# Arduino_Engine_Room.net
KiCad netlist of a schematic drawn in EAGLE
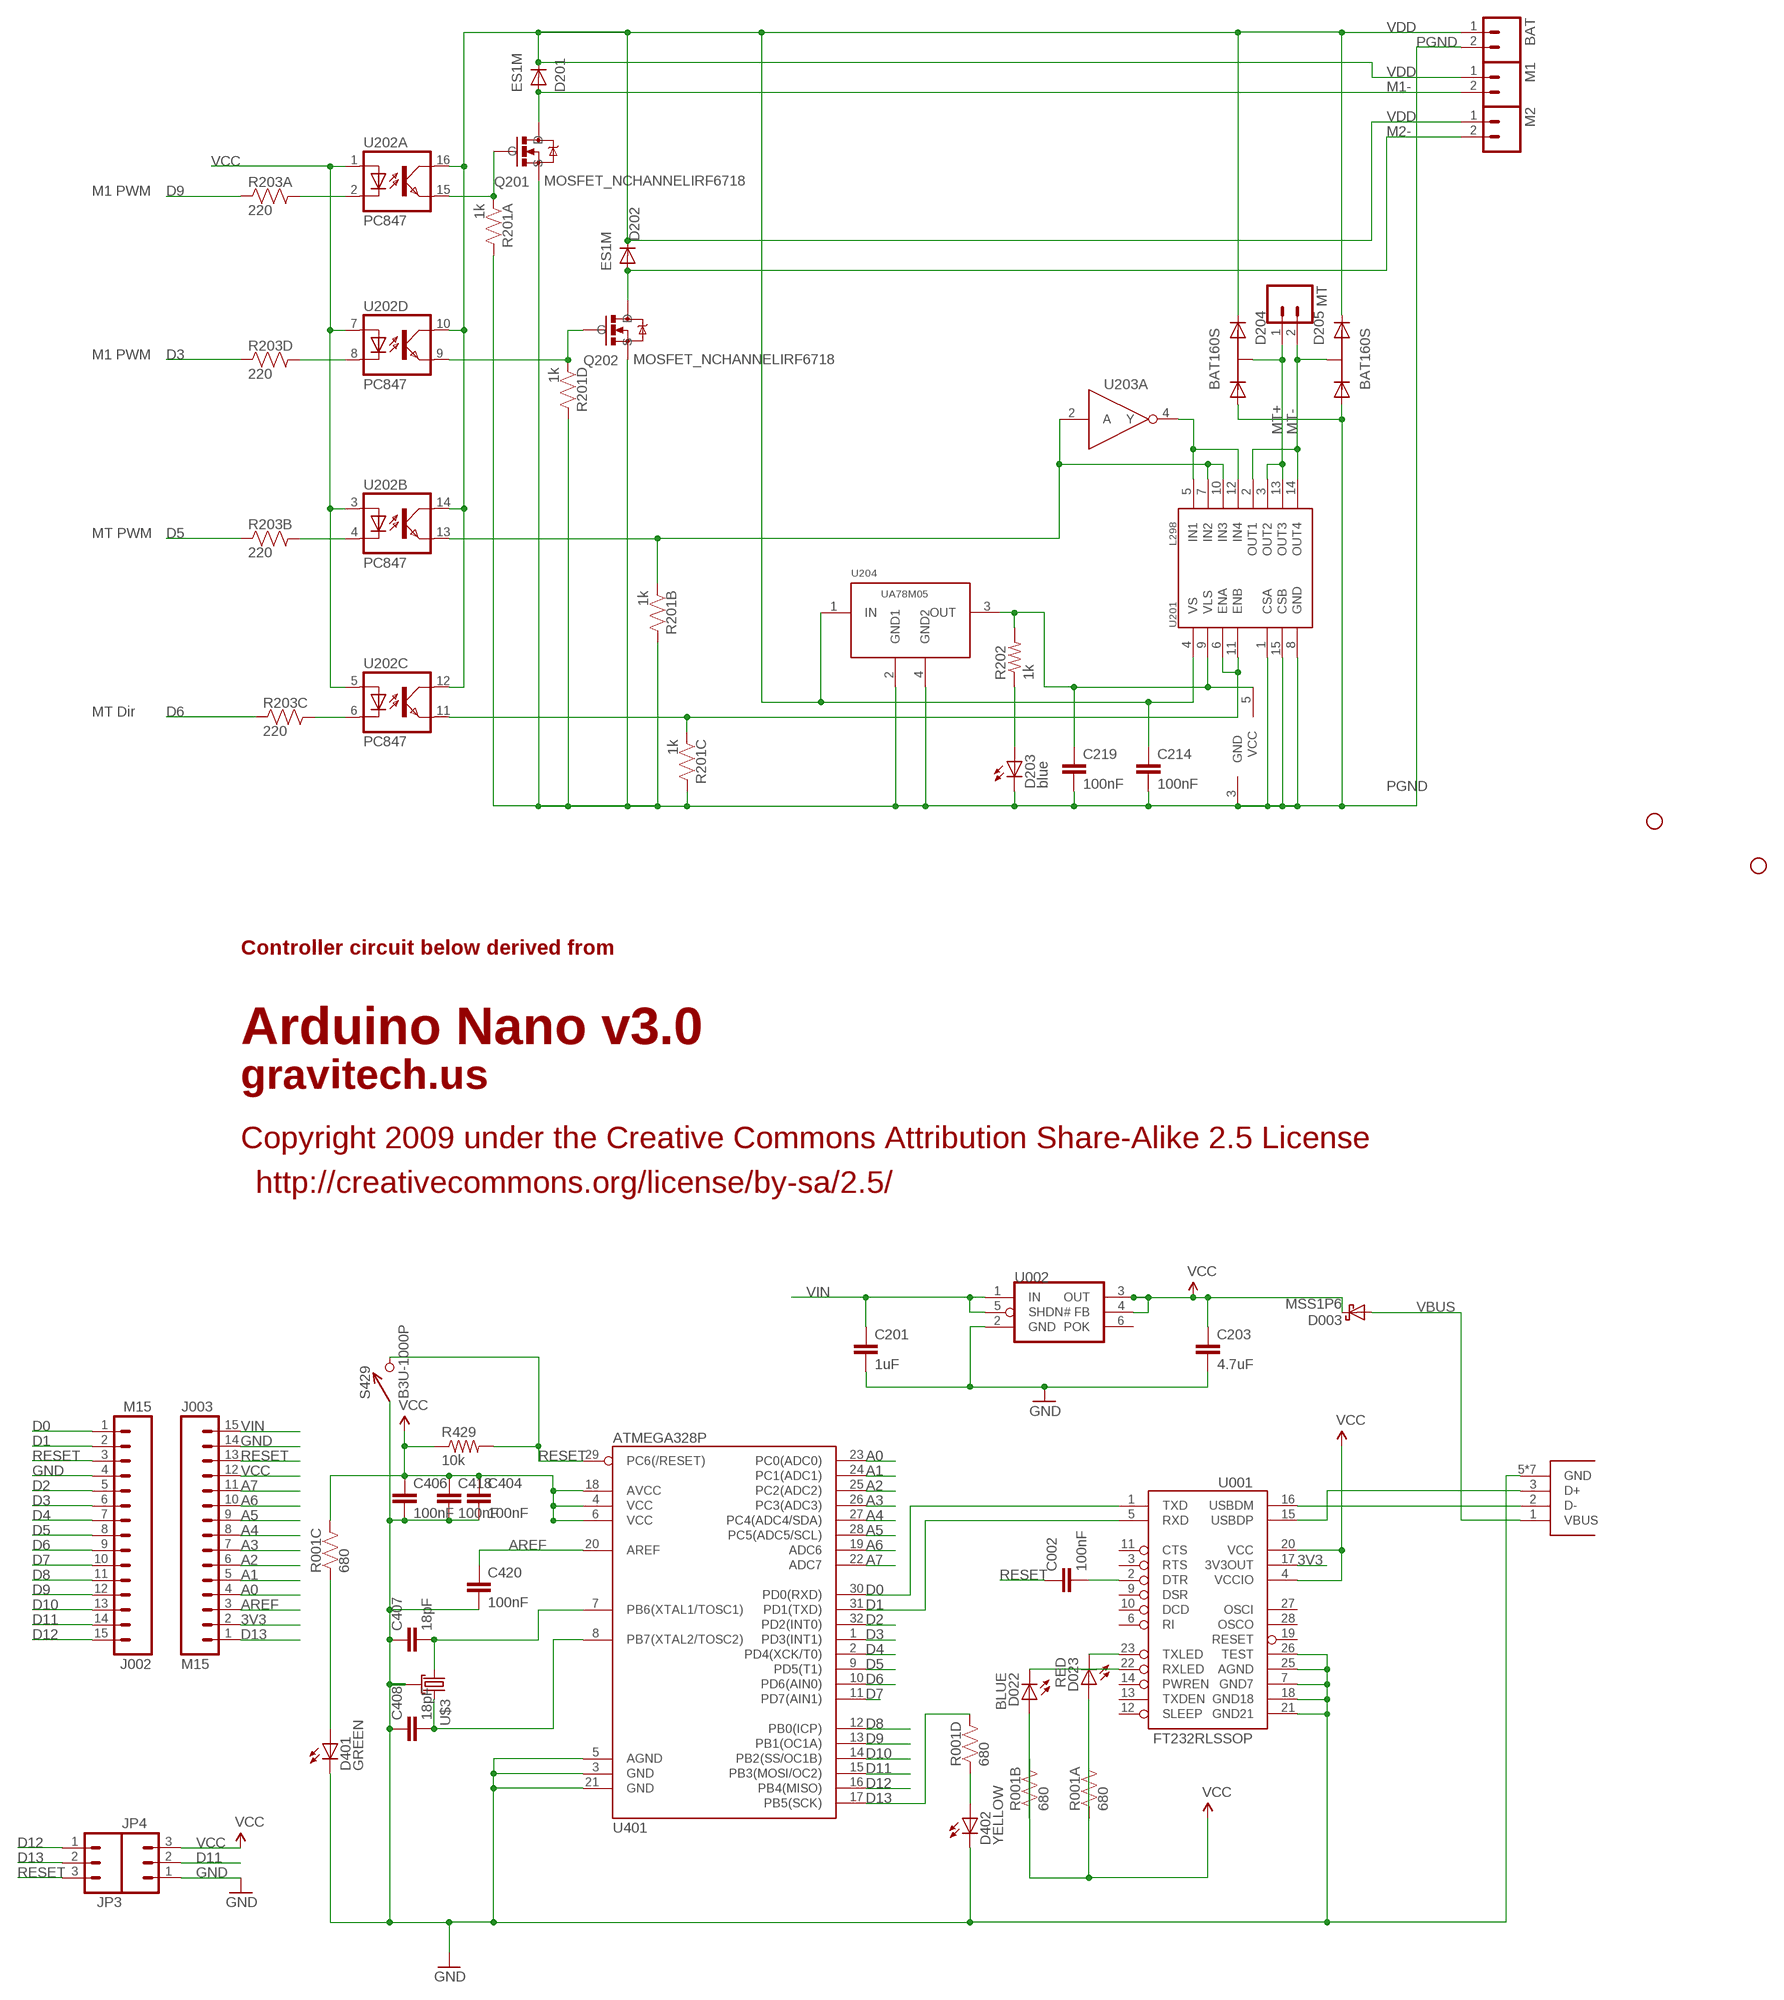
[diagram p0: schematic, sheet 1]

(export (version "E")
  (design (tool "Eeschema 10.0.6"))
  (components
    (comp (ref "BAT")
      (value "M02PTH4")
      (footprint "eagle-import:1X02_XTRA_BIG")
      (libsource (lib "eagle-import") (part "M02PTH4"))
    )
    (comp (ref "C002")
      (value "100nF")
      (footprint "eagle-import:0402-CAP")
      (libsource (lib "eagle-import") (part "CAP0402-CAP"))
    )
    (comp (ref "C201")
      (value "1uF")
      (footprint "eagle-import:0402-CAP")
      (libsource (lib "eagle-import") (part "CAP0402-CAP"))
    )
    (comp (ref "C203")
      (value "4.7uF")
      (footprint "eagle-import:0402-CAP")
      (libsource (lib "eagle-import") (part "CAP0402-CAP"))
    )
    (comp (ref "C214")
      (value "100nF")
      (footprint "eagle-import:0402-CAP")
      (libsource (lib "eagle-import") (part "CAP0402-CAP"))
    )
    (comp (ref "C219")
      (value "100nF")
      (footprint "eagle-import:0402-CAP")
      (libsource (lib "eagle-import") (part "CAP0402-CAP"))
    )
    (comp (ref "C404")
      (value "100nF")
      (footprint "eagle-import:0402-CAP")
      (libsource (lib "eagle-import") (part "CAP0402-CAP"))
    )
    (comp (ref "C406")
      (value "100nF")
      (footprint "eagle-import:0402-CAP")
      (libsource (lib "eagle-import") (part "CAP0402-CAP"))
    )
    (comp (ref "C407")
      (value "18pF")
      (footprint "eagle-import:0402-CAP")
      (libsource (lib "eagle-import") (part "CAP0402-CAP"))
    )
    (comp (ref "C408")
      (value "18pF")
      (footprint "eagle-import:0402-CAP")
      (libsource (lib "eagle-import") (part "CAP0402-CAP"))
    )
    (comp (ref "C418")
      (value "100nF")
      (footprint "eagle-import:0402-CAP")
      (libsource (lib "eagle-import") (part "CAP0402-CAP"))
    )
    (comp (ref "C420")
      (value "100nF")
      (footprint "eagle-import:0402-CAP")
      (libsource (lib "eagle-import") (part "CAP0402-CAP"))
    )
    (comp (ref "D003")
      (value "MSS1P6")
      (footprint "eagle-import:MICROSMP")
      (libsource (lib "eagle-import") (part "MSS1P6"))
    )
    (comp (ref "D022")
      (value "BLUE")
      (footprint "eagle-import:LED-0603")
      (libsource (lib "eagle-import") (part "SparkFun-LED_LED0603"))
    )
    (comp (ref "D023")
      (value "RED")
      (footprint "eagle-import:LED-0603")
      (libsource (lib "eagle-import") (part "SparkFun-LED_LED0603"))
    )
    (comp (ref "D201")
      (value "ES1M")
      (footprint "eagle-import:DO-214AC")
      (libsource (lib "eagle-import") (part "DIODE-DO-214AC"))
    )
    (comp (ref "D202")
      (value "ES1M")
      (footprint "eagle-import:DO-214AC")
      (libsource (lib "eagle-import") (part "DIODE-DO-214AC"))
    )
    (comp (ref "D203")
      (value "blue")
      (footprint "eagle-import:LED-0603")
      (libsource (lib "eagle-import") (part "LED0603"))
    )
    (comp (ref "D204")
      (value "BAT160S")
      (footprint "eagle-import:SOT-223")
      (libsource (lib "eagle-import") (part "BAT160S"))
    )
    (comp (ref "D205")
      (value "BAT160S")
      (footprint "eagle-import:SOT-223")
      (libsource (lib "eagle-import") (part "BAT160S"))
    )
    (comp (ref "D401")
      (value "GREEN")
      (footprint "eagle-import:LED-0603")
      (libsource (lib "eagle-import") (part "SparkFun-LED_LED0603"))
    )
    (comp (ref "D402")
      (value "YELLOW")
      (footprint "eagle-import:LED-0603")
      (libsource (lib "eagle-import") (part "SparkFun-LED_LED0603"))
    )
    (comp (ref "J001")
      (value "USB_MICROB_JSTGCT")
      (footprint "eagle-import:USB_MICROB_3075")
      (libsource (lib "eagle-import") (part "USB_MICROB_JSTGCT"))
    )
    (comp (ref "J002")
      (value "M15")
      (footprint "eagle-import:1X15")
      (libsource (lib "eagle-import") (part "M15"))
    )
    (comp (ref "J003")
      (value "M15")
      (footprint "eagle-import:1X15")
      (libsource (lib "eagle-import") (part "M15"))
    )
    (comp (ref "JP1")
      (value "STAND-OFF")
      (footprint "eagle-import:STAND-OFF")
      (libsource (lib "eagle-import") (part "STAND-OFF"))
    )
    (comp (ref "JP2")
      (value "STAND-OFF")
      (footprint "eagle-import:STAND-OFF")
      (libsource (lib "eagle-import") (part "STAND-OFF"))
    )
    (comp (ref "JP3")
      (value "M03PTH")
      (footprint "eagle-import:1X03")
      (libsource (lib "eagle-import") (part "M03PTH"))
    )
    (comp (ref "JP4")
      (value "M03PTH")
      (footprint "eagle-import:1X03")
      (libsource (lib "eagle-import") (part "M03PTH"))
    )
    (comp (ref "M1")
      (value "M02PTH4")
      (footprint "eagle-import:1X02_XTRA_BIG")
      (libsource (lib "eagle-import") (part "M02PTH4"))
    )
    (comp (ref "M2")
      (value "M02PTH4")
      (footprint "eagle-import:1X02_XTRA_BIG")
      (libsource (lib "eagle-import") (part "M02PTH4"))
    )
    (comp (ref "MT")
      (value "M02PTH")
      (footprint "eagle-import:1X02")
      (libsource (lib "eagle-import") (part "M02PTH"))
    )
    (comp (ref "Q201")
      (value "MOSFET_NCHANNELIRF6718")
      (footprint "eagle-import:DIRECTFET_L6")
      (libsource (lib "eagle-import") (part "MOSFET_NCHANNELIRF6718"))
    )
    (comp (ref "Q202")
      (value "MOSFET_NCHANNELIRF6718")
      (footprint "eagle-import:DIRECTFET_L6")
      (libsource (lib "eagle-import") (part "MOSFET_NCHANNELIRF6718"))
    )
    (comp (ref "R001")
      (value "680")
      (footprint "eagle-import:CRA04")
      (fields (field (name "DIGIKEY") "CRA4S8680CT-ND"))
      (libsource (lib "eagle-import") (part "RP404"))
    )
    (comp (ref "R201")
      (value "1k")
      (footprint "eagle-import:CRA04")
      (libsource (lib "eagle-import") (part "RP404"))
    )
    (comp (ref "R202")
      (value "1k")
      (footprint "eagle-import:0402-RES")
      (libsource (lib "eagle-import") (part "RESISTOR0402-RES"))
    )
    (comp (ref "R203")
      (value "220")
      (footprint "eagle-import:CRA04")
      (libsource (lib "eagle-import") (part "RP404"))
    )
    (comp (ref "R429")
      (value "10k")
      (footprint "eagle-import:0402-RES")
      (libsource (lib "eagle-import") (part "SparkFun-Passives_RESISTOR0402-RES"))
    )
    (comp (ref "S429")
      (value "B3U-1000P")
      (footprint "eagle-import:B3U-1000P")
      (libsource (lib "eagle-import") (part "B3U-1000P"))
    )
    (comp (ref "U$3")
      (value "CX2520")
      (footprint "eagle-import:CRYSTAL_SMD_2MM_2_5MM")
      (libsource (lib "eagle-import") (part "CX2520"))
    )
    (comp (ref "U001")
      (value "FT232RLSSOP")
      (footprint "eagle-import:SSOP28DB")
      (libsource (lib "eagle-import") (part "FT232RLSSOP"))
    )
    (comp (ref "U002")
      (value "MAX8881")
      (footprint "eagle-import:SOT-23-6")
      (libsource (lib "eagle-import") (part "MAX8881"))
    )
    (comp (ref "U201")
      (value "L298")
      (footprint "eagle-import:MULTIWATT15")
      (libsource (lib "eagle-import") (part "L298"))
    )
    (comp (ref "U202")
      (value "PC847")
      (footprint "eagle-import:DIL16")
      (libsource (lib "eagle-import") (part "PC847"))
    )
    (comp (ref "U203")
      (value "MC74VHC1G04")
      (footprint "eagle-import:SOT-23-5")
      (libsource (lib "eagle-import") (part "MC74VHC1G04"))
    )
    (comp (ref "U204")
      (value "UA78M05")
      (footprint "eagle-import:SOT223")
      (libsource (lib "eagle-import") (part "UA78M05"))
    )
    (comp (ref "U401")
      (value "ATMEGA328P")
      (footprint "eagle-import:TQFP32-08")
      (libsource (lib "eagle-import") (part "ATMEGA168"))
    )
  )
  (nets
    (net (code "1") (name "/3V3") (class "Default")
      (node (ref "J003") (pin "2") (pinfunction "2_2") (pintype "passive"))
      (node (ref "U001") (pin "17") (pinfunction "3V3OUT_17") (pintype "output"))
    )
    (net (code "2") (name "/A0") (class "Default")
      (node (ref "J003") (pin "4") (pinfunction "4_4") (pintype "passive"))
      (node (ref "U401") (pin "23") (pinfunction "PC0(ADC0)_23") (pintype "bidirectional"))
    )
    (net (code "3") (name "/A1") (class "Default")
      (node (ref "J003") (pin "5") (pinfunction "5_5") (pintype "passive"))
      (node (ref "U401") (pin "24") (pinfunction "PC1(ADC1)_24") (pintype "bidirectional"))
    )
    (net (code "4") (name "/A2") (class "Default")
      (node (ref "J003") (pin "6") (pinfunction "6_6") (pintype "passive"))
      (node (ref "U401") (pin "25") (pinfunction "PC2(ADC2)_25") (pintype "bidirectional"))
    )
    (net (code "5") (name "/A3") (class "Default")
      (node (ref "J003") (pin "7") (pinfunction "7_7") (pintype "passive"))
      (node (ref "U401") (pin "26") (pinfunction "PC3(ADC3)_26") (pintype "bidirectional"))
    )
    (net (code "6") (name "/A4") (class "Default")
      (node (ref "J003") (pin "8") (pinfunction "8_8") (pintype "passive"))
      (node (ref "U401") (pin "27") (pinfunction "PC4(ADC4/SDA)_27") (pintype "bidirectional"))
    )
    (net (code "7") (name "/A5") (class "Default")
      (node (ref "J003") (pin "9") (pinfunction "9_9") (pintype "passive"))
      (node (ref "U401") (pin "28") (pinfunction "PC5(ADC5/SCL)_28") (pintype "bidirectional"))
    )
    (net (code "8") (name "/A6") (class "Default")
      (node (ref "J003") (pin "10") (pinfunction "10_10") (pintype "passive"))
      (node (ref "U401") (pin "19") (pinfunction "ADC6_19") (pintype "bidirectional"))
    )
    (net (code "9") (name "/A7") (class "Default")
      (node (ref "J003") (pin "11") (pinfunction "11_11") (pintype "passive"))
      (node (ref "U401") (pin "22") (pinfunction "ADC7_22") (pintype "bidirectional"))
    )
    (net (code "10") (name "/AREF") (class "Default")
      (node (ref "C420") (pin "1") (pinfunction "1_1") (pintype "passive"))
      (node (ref "J003") (pin "3") (pinfunction "3_3") (pintype "passive"))
      (node (ref "U401") (pin "20") (pinfunction "AREF_20") (pintype "bidirectional"))
    )
    (net (code "11") (name "/D0") (class "Default")
      (node (ref "J002") (pin "1") (pinfunction "1_1") (pintype "passive"))
      (node (ref "U001") (pin "1") (pinfunction "TXD_1") (pintype "output"))
      (node (ref "U401") (pin "30") (pinfunction "PD0(RXD)_30") (pintype "bidirectional"))
    )
    (net (code "12") (name "/D1") (class "Default")
      (node (ref "J002") (pin "2") (pinfunction "2_2") (pintype "passive"))
      (node (ref "U001") (pin "5") (pinfunction "RXD_5") (pintype "input"))
      (node (ref "U401") (pin "31") (pinfunction "PD1(TXD)_31") (pintype "bidirectional"))
    )
    (net (code "13") (name "/D2") (class "Default")
      (node (ref "J002") (pin "5") (pinfunction "5_5") (pintype "passive"))
      (node (ref "U401") (pin "32") (pinfunction "PD2(INT0)_32") (pintype "bidirectional"))
    )
    (net (code "14") (name "/D3") (class "Default")
      (node (ref "J002") (pin "6") (pinfunction "6_6") (pintype "passive"))
      (node (ref "R203") (pin "4") (pinfunction "1_4") (pintype "passive"))
      (node (ref "U401") (pin "1") (pinfunction "PD3(INT1)_1") (pintype "bidirectional"))
    )
    (net (code "15") (name "/D4") (class "Default")
      (node (ref "J002") (pin "7") (pinfunction "7_7") (pintype "passive"))
      (node (ref "U401") (pin "2") (pinfunction "PD4(XCK/T0)_2") (pintype "bidirectional"))
    )
    (net (code "16") (name "/D5") (class "Default")
      (node (ref "J002") (pin "8") (pinfunction "8_8") (pintype "passive"))
      (node (ref "R203") (pin "2") (pinfunction "1_2") (pintype "passive"))
      (node (ref "U401") (pin "9") (pinfunction "PD5(T1)_9") (pintype "bidirectional"))
    )
    (net (code "17") (name "/D6") (class "Default")
      (node (ref "J002") (pin "9") (pinfunction "9_9") (pintype "passive"))
      (node (ref "R203") (pin "3") (pinfunction "1_3") (pintype "passive"))
      (node (ref "U401") (pin "10") (pinfunction "PD6(AIN0)_10") (pintype "bidirectional"))
    )
    (net (code "18") (name "/D7") (class "Default")
      (node (ref "J002") (pin "10") (pinfunction "10_10") (pintype "passive"))
      (node (ref "U401") (pin "11") (pinfunction "PD7(AIN1)_11") (pintype "bidirectional"))
    )
    (net (code "19") (name "/D8") (class "Default")
      (node (ref "J002") (pin "11") (pinfunction "11_11") (pintype "passive"))
      (node (ref "U401") (pin "12") (pinfunction "PB0(ICP)_12") (pintype "bidirectional"))
    )
    (net (code "20") (name "/D9") (class "Default")
      (node (ref "J002") (pin "12") (pinfunction "12_12") (pintype "passive"))
      (node (ref "R203") (pin "1") (pinfunction "1_1") (pintype "passive"))
      (node (ref "U401") (pin "13") (pinfunction "PB1(OC1A)_13") (pintype "bidirectional"))
    )
    (net (code "21") (name "/D10") (class "Default")
      (node (ref "J002") (pin "13") (pinfunction "13_13") (pintype "passive"))
      (node (ref "U401") (pin "14") (pinfunction "PB2(SS/OC1B)_14") (pintype "bidirectional"))
    )
    (net (code "22") (name "/D11") (class "Default")
      (node (ref "J002") (pin "14") (pinfunction "14_14") (pintype "passive"))
      (node (ref "JP4") (pin "2") (pinfunction "2_2") (pintype "passive"))
      (node (ref "U401") (pin "15") (pinfunction "PB3(MOSI/OC2)_15") (pintype "bidirectional"))
    )
    (net (code "23") (name "/D12") (class "Default")
      (node (ref "J002") (pin "15") (pinfunction "15_15") (pintype "passive"))
      (node (ref "JP3") (pin "1") (pinfunction "1_1") (pintype "passive"))
      (node (ref "U401") (pin "16") (pinfunction "PB4(MISO)_16") (pintype "bidirectional"))
    )
    (net (code "24") (name "/D13") (class "Default")
      (node (ref "J003") (pin "1") (pinfunction "1_1") (pintype "passive"))
      (node (ref "JP3") (pin "2") (pinfunction "2_2") (pintype "passive"))
      (node (ref "R001") (pin "5") (pinfunction "2_5") (pintype "passive"))
      (node (ref "U401") (pin "17") (pinfunction "PB5(SCK)_17") (pintype "bidirectional"))
    )
    (net (code "25") (name "/M1-") (class "Default")
      (node (ref "D201") (pin "A") (pinfunction "A_A") (pintype "passive"))
      (node (ref "M1") (pin "2") (pinfunction "2_2") (pintype "passive"))
      (node (ref "Q201") (pin "D1") (pinfunction "D_D1") (pintype "passive"))
      (node (ref "Q201") (pin "D2") (pinfunction "D_D2") (pintype "passive"))
    )
    (net (code "26") (name "/M2-") (class "Default")
      (node (ref "D202") (pin "A") (pinfunction "A_A") (pintype "passive"))
      (node (ref "M2") (pin "2") (pinfunction "2_2") (pintype "passive"))
      (node (ref "Q202") (pin "D1") (pinfunction "D_D1") (pintype "passive"))
      (node (ref "Q202") (pin "D2") (pinfunction "D_D2") (pintype "passive"))
    )
    (net (code "27") (name "/MT+") (class "Default")
      (node (ref "D204") (pin "4") (pinfunction "K1A2_4") (pintype "passive"))
      (node (ref "MT") (pin "1") (pinfunction "1_1") (pintype "passive"))
      (node (ref "U201") (pin "13") (pinfunction "OUT3_13") (pintype "bidirectional"))
      (node (ref "U201") (pin "3") (pinfunction "OUT2_3") (pintype "bidirectional"))
    )
    (net (code "28") (name "/MT-") (class "Default")
      (node (ref "D205") (pin "4") (pinfunction "K1A2_4") (pintype "passive"))
      (node (ref "MT") (pin "2") (pinfunction "2_2") (pintype "passive"))
      (node (ref "U201") (pin "14") (pinfunction "OUT4_14") (pintype "bidirectional"))
      (node (ref "U201") (pin "2") (pinfunction "OUT1_2") (pintype "bidirectional"))
    )
    (net (code "29") (name "/PGND") (class "Default")
      (node (ref "BAT") (pin "2") (pinfunction "2_2") (pintype "passive"))
      (node (ref "C214") (pin "2") (pinfunction "2_2") (pintype "passive"))
      (node (ref "C219") (pin "2") (pinfunction "2_2") (pintype "passive"))
      (node (ref "D203") (pin "C") (pinfunction "C_C") (pintype "passive"))
      (node (ref "D204") (pin "1") (pinfunction "A1_1") (pintype "passive"))
      (node (ref "D205") (pin "1") (pinfunction "A1_1") (pintype "passive"))
      (node (ref "Q201") (pin "S") (pinfunction "S_S") (pintype "passive"))
      (node (ref "Q202") (pin "S") (pinfunction "S_S") (pintype "passive"))
      (node (ref "R201") (pin "5") (pinfunction "2_5") (pintype "passive"))
      (node (ref "R201") (pin "6") (pinfunction "2_6") (pintype "passive"))
      (node (ref "R201") (pin "7") (pinfunction "2_7") (pintype "passive"))
      (node (ref "R201") (pin "8") (pinfunction "2_8") (pintype "passive"))
      (node (ref "U201") (pin "1") (pinfunction "CSA_1") (pintype "bidirectional"))
      (node (ref "U201") (pin "15") (pinfunction "CSB_15") (pintype "bidirectional"))
      (node (ref "U201") (pin "8") (pinfunction "GND_8") (pintype "bidirectional"))
      (node (ref "U203") (pin "3") (pinfunction "GND_3") (pintype "bidirectional"))
      (node (ref "U204") (pin "2") (pinfunction "GND1_2") (pintype "power_in"))
      (node (ref "U204") (pin "4") (pinfunction "GND2_4") (pintype "power_in"))
    )
    (net (code "30") (name "/RESET") (class "Default")
      (node (ref "C002") (pin "1") (pinfunction "1_1") (pintype "passive"))
      (node (ref "J002") (pin "3") (pinfunction "3_3") (pintype "passive"))
      (node (ref "J003") (pin "13") (pinfunction "13_13") (pintype "passive"))
      (node (ref "JP3") (pin "3") (pinfunction "3_3") (pintype "passive"))
      (node (ref "R429") (pin "2") (pinfunction "2_2") (pintype "passive"))
      (node (ref "S429") (pin "P$2") (pinfunction "2_P$2") (pintype "bidirectional"))
      (node (ref "U401") (pin "29") (pinfunction "PC6(/RESET)_29") (pintype "bidirectional"))
    )
    (net (code "31") (name "/VBUS") (class "Default")
      (node (ref "D003") (pin "A") (pinfunction "A_A") (pintype "passive"))
      (node (ref "J001") (pin "1") (pinfunction "VBUS_1") (pintype "bidirectional"))
    )
    (net (code "32") (name "/VDD") (class "Default")
      (node (ref "BAT") (pin "1") (pinfunction "1_1") (pintype "passive"))
      (node (ref "C214") (pin "1") (pinfunction "1_1") (pintype "passive"))
      (node (ref "D201") (pin "C") (pinfunction "C_C") (pintype "passive"))
      (node (ref "D202") (pin "C") (pinfunction "C_C") (pintype "passive"))
      (node (ref "D204") (pin "3") (pinfunction "K2_3") (pintype "passive"))
      (node (ref "D205") (pin "3") (pinfunction "K2_3") (pintype "passive"))
      (node (ref "M1") (pin "1") (pinfunction "1_1") (pintype "passive"))
      (node (ref "M2") (pin "1") (pinfunction "1_1") (pintype "passive"))
      (node (ref "U201") (pin "4") (pinfunction "VS_4") (pintype "bidirectional"))
      (node (ref "U202") (pin "10") (pinfunction "COL_10") (pintype "passive"))
      (node (ref "U202") (pin "12") (pinfunction "COL_12") (pintype "passive"))
      (node (ref "U202") (pin "14") (pinfunction "COL_14") (pintype "passive"))
      (node (ref "U202") (pin "16") (pinfunction "COL_16") (pintype "passive"))
      (node (ref "U204") (pin "1") (pinfunction "IN_1") (pintype "power_in"))
    )
    (net (code "33") (name "/VIN") (class "Default")
      (node (ref "C201") (pin "1") (pinfunction "1_1") (pintype "passive"))
      (node (ref "J003") (pin "15") (pinfunction "15_15") (pintype "passive"))
      (node (ref "U002") (pin "1") (pinfunction "IN_1") (pintype "bidirectional"))
      (node (ref "U002") (pin "5") (pinfunction "SHDN#_5") (pintype "bidirectional"))
    )
    (net (code "34") (name "GND") (class "Default")
      (node (ref "C201") (pin "2") (pinfunction "2_2") (pintype "passive"))
      (node (ref "C203") (pin "2") (pinfunction "2_2") (pintype "passive"))
      (node (ref "C404") (pin "2") (pinfunction "2_2") (pintype "passive"))
      (node (ref "C406") (pin "2") (pinfunction "2_2") (pintype "passive"))
      (node (ref "C407") (pin "1") (pinfunction "1_1") (pintype "passive"))
      (node (ref "C408") (pin "1") (pinfunction "1_1") (pintype "passive"))
      (node (ref "C418") (pin "2") (pinfunction "2_2") (pintype "passive"))
      (node (ref "C420") (pin "2") (pinfunction "2_2") (pintype "passive"))
      (node (ref "D401") (pin "C") (pinfunction "C_C") (pintype "passive"))
      (node (ref "D402") (pin "C") (pinfunction "C_C") (pintype "passive"))
      (node (ref "J001") (pin "5") (pinfunction "GND_5") (pintype "bidirectional"))
      (node (ref "J001") (pin "P$1") (pinfunction "GND_P$1") (pintype "bidirectional"))
      (node (ref "J001") (pin "P$10") (pinfunction "GND_P$10") (pintype "bidirectional"))
      (node (ref "J001") (pin "P$2") (pinfunction "GND_P$2") (pintype "bidirectional"))
      (node (ref "J001") (pin "P$3") (pinfunction "GND_P$3") (pintype "bidirectional"))
      (node (ref "J001") (pin "P$4") (pinfunction "GND_P$4") (pintype "bidirectional"))
      (node (ref "J001") (pin "P$8") (pinfunction "GND_P$8") (pintype "bidirectional"))
      (node (ref "J002") (pin "4") (pinfunction "4_4") (pintype "passive"))
      (node (ref "J003") (pin "14") (pinfunction "14_14") (pintype "passive"))
      (node (ref "JP4") (pin "1") (pinfunction "1_1") (pintype "passive"))
      (node (ref "S429") (pin "P$1") (pinfunction "1_P$1") (pintype "bidirectional"))
      (node (ref "U$3") (pin "2") (pinfunction "GND_2") (pintype "passive"))
      (node (ref "U$3") (pin "4") (pinfunction "GND_4") (pintype "passive"))
      (node (ref "U001") (pin "18") (pinfunction "GND18_18") (pintype "power_in"))
      (node (ref "U001") (pin "21") (pinfunction "GND21_21") (pintype "power_in"))
      (node (ref "U001") (pin "25") (pinfunction "AGND_25") (pintype "power_in"))
      (node (ref "U001") (pin "26") (pinfunction "TEST_26") (pintype "input"))
      (node (ref "U001") (pin "7") (pinfunction "GND7_7") (pintype "power_in"))
      (node (ref "U002") (pin "2") (pinfunction "GND_2") (pintype "bidirectional"))
      (node (ref "U401") (pin "21") (pinfunction "GND_21") (pintype "bidirectional"))
      (node (ref "U401") (pin "3") (pinfunction "GND_3") (pintype "bidirectional"))
      (node (ref "U401") (pin "5") (pinfunction "AGND_5") (pintype "bidirectional"))
    )
    (net (code "35") (name "Net-(D023-PadA)") (class "Default")
      (node (ref "D023") (pin "A") (pinfunction "A_A") (pintype "passive"))
      (node (ref "R001") (pin "1") (pinfunction "1_1") (pintype "passive"))
    )
    (net (code "36") (name "Net-(D203-PadA)") (class "Default")
      (node (ref "D203") (pin "A") (pinfunction "A_A") (pintype "passive"))
      (node (ref "R202") (pin "1") (pinfunction "1_1") (pintype "passive"))
    )
    (net (code "37") (name "Net-(J001-D+)") (class "Default")
      (node (ref "J001") (pin "3") (pinfunction "D+_3") (pintype "bidirectional"))
      (node (ref "U001") (pin "15") (pinfunction "USBDP_15") (pintype "bidirectional"))
    )
    (net (code "38") (name "Net-(J001-D-)") (class "Default")
      (node (ref "J001") (pin "2") (pinfunction "D-_2") (pintype "bidirectional"))
      (node (ref "U001") (pin "16") (pinfunction "USBDM_16") (pintype "bidirectional"))
    )
    (net (code "39") (name "Net-(R001B-1)") (class "Default")
      (node (ref "D022") (pin "A") (pinfunction "A_A") (pintype "passive"))
      (node (ref "R001") (pin "2") (pinfunction "1_2") (pintype "passive"))
    )
    (net (code "40") (name "Net-(R001C-1)") (class "Default")
      (node (ref "D401") (pin "A") (pinfunction "A_A") (pintype "passive"))
      (node (ref "R001") (pin "3") (pinfunction "1_3") (pintype "passive"))
    )
    (net (code "41") (name "Net-(R001D-1)") (class "Default")
      (node (ref "D402") (pin "A") (pinfunction "A_A") (pintype "passive"))
      (node (ref "R001") (pin "4") (pinfunction "1_4") (pintype "passive"))
    )
    (net (code "42") (name "Net-(R201B-1)") (class "Default")
      (node (ref "R201") (pin "2") (pinfunction "1_2") (pintype "passive"))
      (node (ref "U201") (pin "10") (pinfunction "IN3_10") (pintype "bidirectional"))
      (node (ref "U201") (pin "7") (pinfunction "IN2_7") (pintype "bidirectional"))
      (node (ref "U202") (pin "13") (pinfunction "EMIT_13") (pintype "passive"))
      (node (ref "U203") (pin "2") (pinfunction "A_2") (pintype "input"))
    )
    (net (code "43") (name "Net-(R201C-1)") (class "Default")
      (node (ref "R201") (pin "3") (pinfunction "1_3") (pintype "passive"))
      (node (ref "U201") (pin "11") (pinfunction "ENB_11") (pintype "bidirectional"))
      (node (ref "U201") (pin "6") (pinfunction "ENA_6") (pintype "bidirectional"))
      (node (ref "U202") (pin "11") (pinfunction "EMIT_11") (pintype "passive"))
    )
    (net (code "44") (name "Net-(R201D-1)") (class "Default")
      (node (ref "Q202") (pin "G") (pinfunction "G_G") (pintype "passive"))
      (node (ref "R201") (pin "4") (pinfunction "1_4") (pintype "passive"))
      (node (ref "U202") (pin "9") (pinfunction "EMIT_9") (pintype "passive"))
    )
    (net (code "45") (name "Net-(R203A-2)") (class "Default")
      (node (ref "R203") (pin "8") (pinfunction "2_8") (pintype "passive"))
      (node (ref "U202") (pin "2") (pinfunction "C_2") (pintype "passive"))
    )
    (net (code "46") (name "Net-(R203B-2)") (class "Default")
      (node (ref "R203") (pin "7") (pinfunction "2_7") (pintype "passive"))
      (node (ref "U202") (pin "4") (pinfunction "C_4") (pintype "passive"))
    )
    (net (code "47") (name "Net-(R203C-2)") (class "Default")
      (node (ref "R203") (pin "6") (pinfunction "2_6") (pintype "passive"))
      (node (ref "U202") (pin "6") (pinfunction "C_6") (pintype "passive"))
    )
    (net (code "48") (name "Net-(R203D-2)") (class "Default")
      (node (ref "R203") (pin "5") (pinfunction "2_5") (pintype "passive"))
      (node (ref "U202") (pin "8") (pinfunction "C_8") (pintype "passive"))
    )
    (net (code "49") (name "Net-(U$3-2)") (class "Default")
      (node (ref "C408") (pin "2") (pinfunction "2_2") (pintype "passive"))
      (node (ref "U$3") (pin "3") (pinfunction "2_3") (pintype "passive"))
      (node (ref "U401") (pin "8") (pinfunction "PB7(XTAL2/TOSC2)_8") (pintype "bidirectional"))
    )
    (net (code "50") (name "Net-(U001-DTR)") (class "Default")
      (node (ref "C002") (pin "2") (pinfunction "2_2") (pintype "passive"))
      (node (ref "U001") (pin "2") (pinfunction "DTR_2") (pintype "output"))
    )
    (net (code "51") (name "Net-(U001-RXLED)") (class "Default")
      (node (ref "D022") (pin "C") (pinfunction "C_C") (pintype "passive"))
      (node (ref "U001") (pin "22") (pinfunction "RXLED_22") (pintype "input"))
    )
    (net (code "52") (name "Net-(U001-TXLED)") (class "Default")
      (node (ref "D023") (pin "C") (pinfunction "C_C") (pintype "passive"))
      (node (ref "U001") (pin "23") (pinfunction "TXLED_23") (pintype "input"))
    )
    (net (code "53") (name "Net-(U201-IN1)") (class "Default")
      (node (ref "U201") (pin "12") (pinfunction "IN4_12") (pintype "bidirectional"))
      (node (ref "U201") (pin "5") (pinfunction "IN1_5") (pintype "bidirectional"))
      (node (ref "U203") (pin "4") (pinfunction "Y_4") (pintype "output"))
    )
    (net (code "54") (name "Net-(U201-VLS)") (class "Default")
      (node (ref "C219") (pin "1") (pinfunction "1_1") (pintype "passive"))
      (node (ref "R202") (pin "2") (pinfunction "2_2") (pintype "passive"))
      (node (ref "U201") (pin "9") (pinfunction "VLS_9") (pintype "bidirectional"))
      (node (ref "U203") (pin "5") (pinfunction "VCC_5") (pintype "bidirectional"))
      (node (ref "U204") (pin "3") (pinfunction "OUT_3") (pintype "power_in"))
    )
    (net (code "55") (name "Net-(U202A-EMIT)") (class "Default")
      (node (ref "Q201") (pin "G") (pinfunction "G_G") (pintype "passive"))
      (node (ref "R201") (pin "1") (pinfunction "1_1") (pintype "passive"))
      (node (ref "U202") (pin "15") (pinfunction "EMIT_15") (pintype "passive"))
    )
    (net (code "56") (name "Net-(U401-PB6(XTAL1{slash}TOSC1))") (class "Default")
      (node (ref "C407") (pin "2") (pinfunction "2_2") (pintype "passive"))
      (node (ref "U$3") (pin "1") (pinfunction "1_1") (pintype "passive"))
      (node (ref "U401") (pin "7") (pinfunction "PB6(XTAL1/TOSC1)_7") (pintype "bidirectional"))
    )
    (net (code "57") (name "VCC") (class "Default")
      (node (ref "C203") (pin "1") (pinfunction "1_1") (pintype "passive"))
      (node (ref "C404") (pin "1") (pinfunction "1_1") (pintype "passive"))
      (node (ref "C406") (pin "1") (pinfunction "1_1") (pintype "passive"))
      (node (ref "C418") (pin "1") (pinfunction "1_1") (pintype "passive"))
      (node (ref "D003") (pin "K") (pinfunction "K_K") (pintype "passive"))
      (node (ref "J003") (pin "12") (pinfunction "12_12") (pintype "passive"))
      (node (ref "JP4") (pin "3") (pinfunction "3_3") (pintype "passive"))
      (node (ref "R001") (pin "6") (pinfunction "2_6") (pintype "passive"))
      (node (ref "R001") (pin "7") (pinfunction "2_7") (pintype "passive"))
      (node (ref "R001") (pin "8") (pinfunction "2_8") (pintype "passive"))
      (node (ref "R429") (pin "1") (pinfunction "1_1") (pintype "passive"))
      (node (ref "U001") (pin "20") (pinfunction "VCC_20") (pintype "power_in"))
      (node (ref "U001") (pin "4") (pinfunction "VCCIO_4") (pintype "power_in"))
      (node (ref "U002") (pin "3") (pinfunction "OUT_3") (pintype "bidirectional"))
      (node (ref "U002") (pin "4") (pinfunction "FB_4") (pintype "bidirectional"))
      (node (ref "U202") (pin "1") (pinfunction "A_1") (pintype "passive"))
      (node (ref "U202") (pin "3") (pinfunction "A_3") (pintype "passive"))
      (node (ref "U202") (pin "5") (pinfunction "A_5") (pintype "passive"))
      (node (ref "U202") (pin "7") (pinfunction "A_7") (pintype "passive"))
      (node (ref "U401") (pin "18") (pinfunction "AVCC_18") (pintype "bidirectional"))
      (node (ref "U401") (pin "4") (pinfunction "VCC_4") (pintype "bidirectional"))
      (node (ref "U401") (pin "6") (pinfunction "VCC_6") (pintype "bidirectional"))
    )
    (net (code "58") (name "unconnected-(U001-CTS-Pad11)") (class "Default")
      (node (ref "U001") (pin "11") (pinfunction "CTS_11") (pintype "input"))
    )
    (net (code "59") (name "unconnected-(U001-DCD-Pad10)") (class "Default")
      (node (ref "U001") (pin "10") (pinfunction "DCD_10") (pintype "input"))
    )
    (net (code "60") (name "unconnected-(U001-DSR-Pad9)") (class "Default")
      (node (ref "U001") (pin "9") (pinfunction "DSR_9") (pintype "input"))
    )
    (net (code "61") (name "unconnected-(U001-OSCI-Pad27)") (class "Default")
      (node (ref "U001") (pin "27") (pinfunction "OSCI_27") (pintype "input"))
    )
    (net (code "62") (name "unconnected-(U001-OSCO-Pad28)") (class "Default")
      (node (ref "U001") (pin "28") (pinfunction "OSCO_28") (pintype "output"))
    )
    (net (code "63") (name "unconnected-(U001-PWREN-Pad14)") (class "Default")
      (node (ref "U001") (pin "14") (pinfunction "PWREN_14") (pintype "input"))
    )
    (net (code "64") (name "unconnected-(U001-RESET-Pad19)") (class "Default")
      (node (ref "U001") (pin "19") (pinfunction "RESET_19") (pintype "input"))
    )
    (net (code "65") (name "unconnected-(U001-RI-Pad6)") (class "Default")
      (node (ref "U001") (pin "6") (pinfunction "RI_6") (pintype "input"))
    )
    (net (code "66") (name "unconnected-(U001-RTS-Pad3)") (class "Default")
      (node (ref "U001") (pin "3") (pinfunction "RTS_3") (pintype "output"))
    )
    (net (code "67") (name "unconnected-(U001-SLEEP-Pad12)") (class "Default")
      (node (ref "U001") (pin "12") (pinfunction "SLEEP_12") (pintype "input"))
    )
    (net (code "68") (name "unconnected-(U001-TXDEN-Pad13)") (class "Default")
      (node (ref "U001") (pin "13") (pinfunction "TXDEN_13") (pintype "input"))
    )
    (net (code "69") (name "unconnected-(U002-POK-Pad6)") (class "Default")
      (node (ref "U002") (pin "6") (pinfunction "POK_6") (pintype "bidirectional"))
    )
  )
)
